# Power_Delivery.net
KiCad netlist of a schematic drawn in Altium Designer
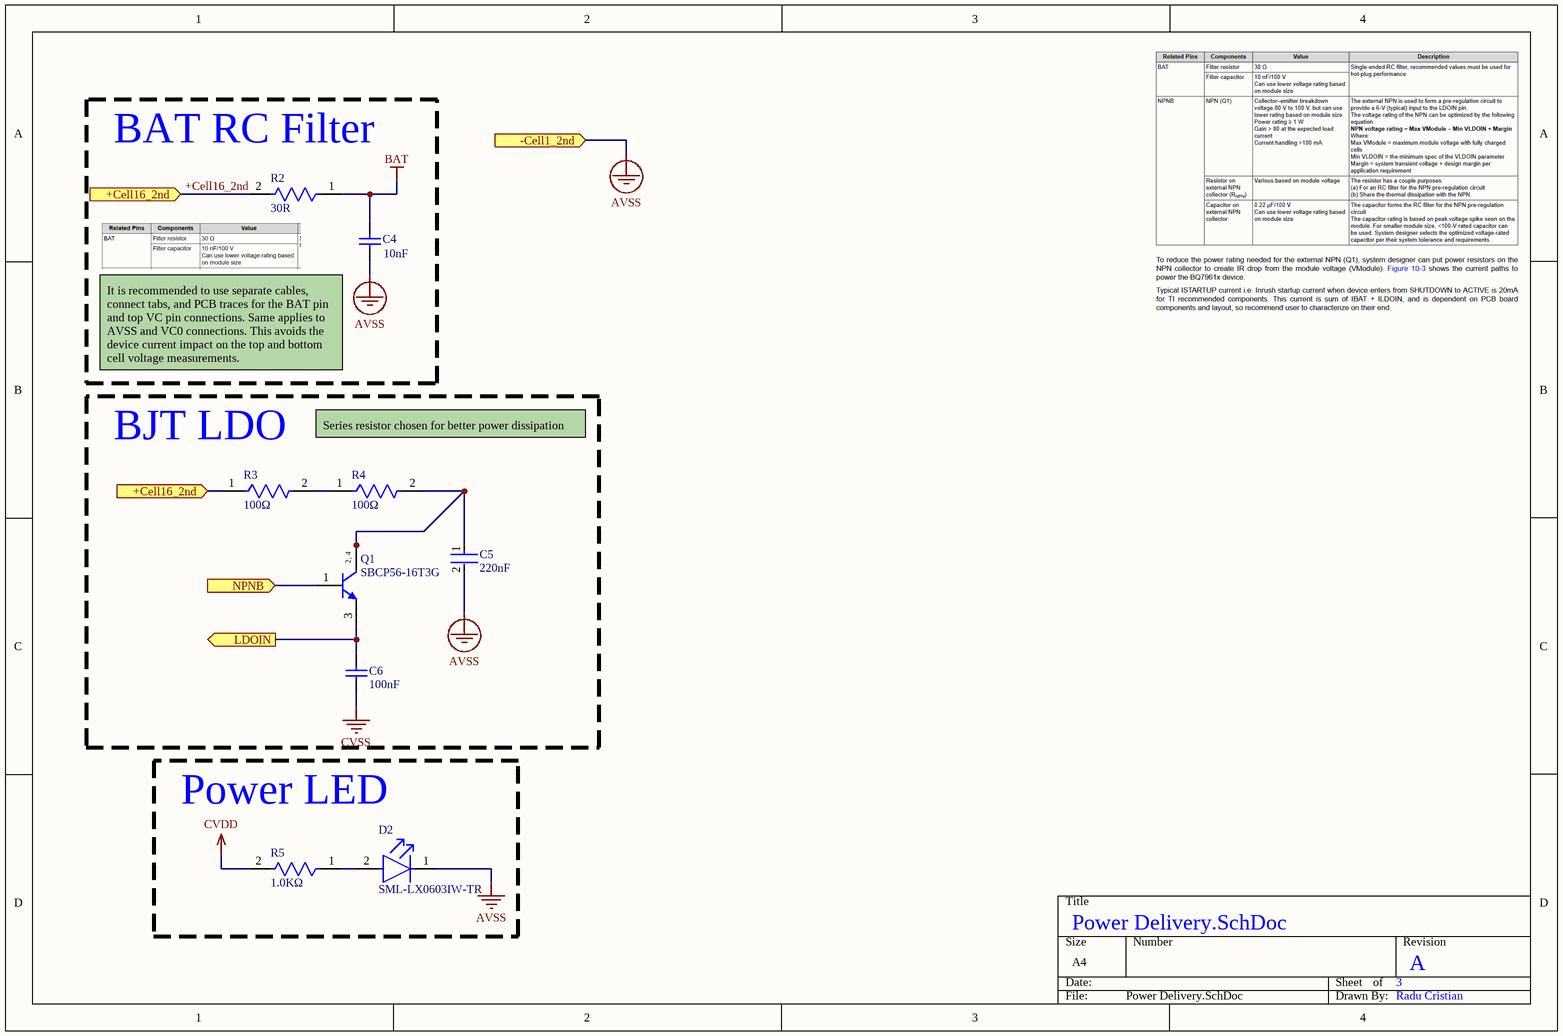
[diagram p0: Power Delivery.SchDoc]

(export (version "E")
  (design (tool "Eeschema 10.0.6"))
  (components
    (comp (ref "C4")
      (value "VJ0603Y103JXBAC")
      (footprint "CAPC1608X92X38LL15T08")
      (fields (field (name "MANUFACTURER") "Vitramon") (field (name "PARAMETER 1") "10nF"))
      (libsource (lib "Altium Content Vault") (part "CAP"))
    )
    (comp (ref "C5")
      (value "08051C224K4T2A")
      (footprint "FP-0805-L_2_01_0_2-W_1_25-MFG")
      (description "Automotive Ceramic Capacitor, 0805, 220nF, 10%, X7R, 15%, 100V")
      (fields (field (name "CAPACITANCE") "220nF") (field (name "TOLERANCE") "10%"))
      (libsource (lib "Altium Content Vault") (part "b4654b650e69147ec39a6b967a45e02"))
    )
    (comp (ref "C6")
      (value "VJ0603Y104KXAAT")
      (footprint "CAPC1608X92X38ML15T08")
      (fields (field (name "MANUFACTURER") "Vishay") (field (name "PARAMETER 1") "100nF"))
      (libsource (lib "Altium Content Vault") (part "CAP"))
    )
    (comp (ref "D2")
      (value "SML-LX0603IW-TR")
      (footprint "FP-SML-LX0603IW-TR-MFG")
      (description "LED RED DIFFUSED SMD")
      (libsource (lib "Altium Content Vault") (part "8706943c75ba83719d021d2fdc84c58"))
    )
    (comp (ref "Q1")
      (value "SBCP56-16T3G")
      (footprint "ONSC-SOT-223-4-318E-04_V")
      (description "NPN Silicon Epitaxial Transistor, 4-Pin SOT-223, Pb-Free, Tape and Reel")
      (fields (field (name "MANUFACTURER") "On Semiconductor"))
      (libsource (lib "Altium Content Vault") (part "ONSC-NPN-B1C2E3C4-4"))
    )
    (comp (ref "R2")
      (value "AC0603FR-0730RL")
      (footprint "FP-AC0603-IPC_C")
      (description "RES 30Ω 1.00% 0.1W 0603")
      (fields (field (name "TOLERANCE") "1%") (field (name "RESISTANCE") "30R"))
      (libsource (lib "Altium Content Vault") (part "1029c3af85768c4190bb7ad29bc67b5"))
    )
    (comp (ref "R3")
      (value "SR0805FR-47100RL")
      (footprint "FP-SR0805-MFG")
      (description "RES 100 OHM 1% 1/2W 0805")
      (fields
        (field (name "TOLERANCE") "0.01")
        (field (name "OCTOPART") "https://octopart.com/sr0805fr-47100rl-yageo-91478093")
        (field (name "RESISTANCE") "100Ω")
      )
      (libsource (lib "Altium Content Vault") (part "1029c3af85768c4190bb7ad29bc67b5"))
    )
    (comp (ref "R4")
      (value "SR0805FR-47100RL")
      (footprint "FP-SR0805-MFG")
      (description "RES 100 OHM 1% 1/2W 0805")
      (fields
        (field (name "TOLERANCE") "0.01")
        (field (name "OCTOPART") "https://octopart.com/sr0805fr-47100rl-yageo-91478093")
        (field (name "RESISTANCE") "100Ω")
      )
      (libsource (lib "Altium Content Vault") (part "1029c3af85768c4190bb7ad29bc67b5"))
    )
    (comp (ref "R5")
      (value "CPF0603F1K0C1")
      (footprint "FP-CPF0603-MFG")
      (description "RES SMD 1.0KΩ 1% 1/16W 0603")
      (fields
        (field (name "OCTOPART") "https://octopart.com/cpf0603f1k0c1-te+connectivity-42013134")
        (field (name "TOLERANCE") "1%")
        (field (name "RESISTANCE") "1.0KΩ")
      )
      (libsource (lib "Altium Content Vault") (part "1029c3af85768c4190bb7ad29bc67b5"))
    )
  )
  (nets
    (net (code "1") (name "/+Cell16_2nd") (class "Default")
      (node (ref "R2") (pin "2") (pinfunction "2_2") (pintype "passive"))
      (node (ref "R3") (pin "1") (pinfunction "1_1") (pintype "passive"))
    )
    (net (code "2") (name "/LDOIN") (class "Default")
      (node (ref "C6") (pin "2") (pinfunction "2_2") (pintype "passive"))
      (node (ref "Q1") (pin "3") (pinfunction "E_3") (pintype "passive"))
    )
    (net (code "3") (name "/NPNB") (class "Default")
      (node (ref "Q1") (pin "1") (pinfunction "B_1") (pintype "passive"))
    )
    (net (code "4") (name "AVSS") (class "Default")
      (node (ref "C4") (pin "1") (pinfunction "1_1") (pintype "passive"))
      (node (ref "C5") (pin "2") (pinfunction "2_2") (pintype "passive"))
      (node (ref "D2") (pin "1") (pinfunction "C_1") (pintype "passive"))
    )
    (net (code "5") (name "BAT") (class "Default")
      (node (ref "C4") (pin "2") (pinfunction "2_2") (pintype "passive"))
      (node (ref "R2") (pin "1") (pinfunction "1_1") (pintype "passive"))
    )
    (net (code "6") (name "CVDD") (class "Default")
      (node (ref "R5") (pin "2") (pinfunction "2_2") (pintype "passive"))
    )
    (net (code "7") (name "CVSS") (class "Default")
      (node (ref "C6") (pin "1") (pinfunction "1_1") (pintype "passive"))
    )
    (net (code "8") (name "Net-(C5-Pad1)") (class "Default")
      (node (ref "C5") (pin "1") (pinfunction "1_1") (pintype "passive"))
      (node (ref "Q1") (pin "2") (pinfunction "C_2") (pintype "passive"))
      (node (ref "Q1") (pin "4") (pinfunction "C_4") (pintype "passive"))
      (node (ref "R4") (pin "2") (pinfunction "2_2") (pintype "passive"))
    )
    (net (code "9") (name "Net-(D2-A)") (class "Default")
      (node (ref "D2") (pin "2") (pinfunction "A_2") (pintype "passive"))
      (node (ref "R5") (pin "1") (pinfunction "1_1") (pintype "passive"))
    )
    (net (code "10") (name "Net-(R3-Pad2)") (class "Default")
      (node (ref "R3") (pin "2") (pinfunction "2_2") (pintype "passive"))
      (node (ref "R4") (pin "1") (pinfunction "1_1") (pintype "passive"))
    )
  )
)
